# ring_counter.net
KiCad netlist of a schematic drawn in EAGLE
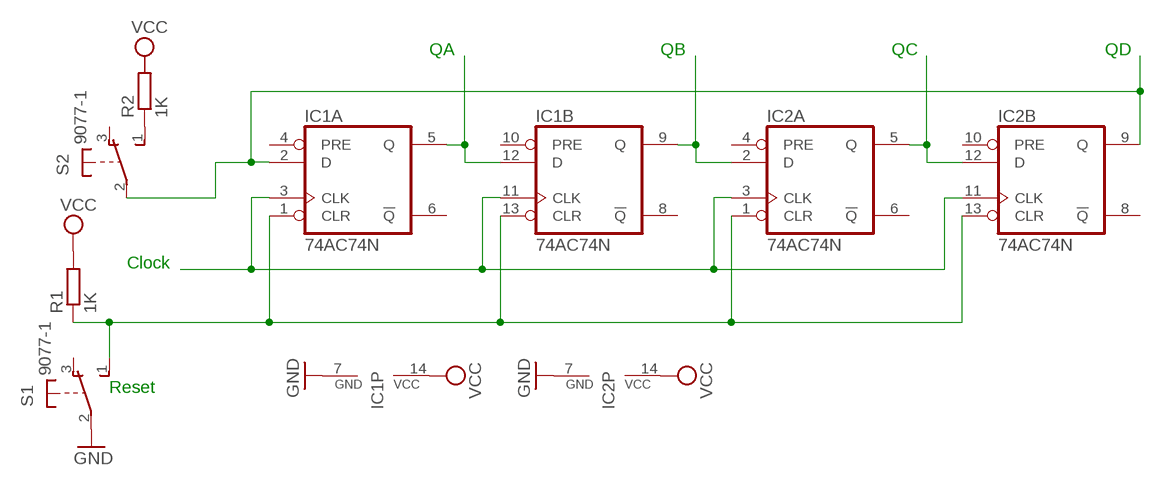
[diagram p0: schematic, sheet 1]

(export (version "E")
  (design (tool "Eeschema 10.0.6"))
  (components
    (comp (ref "IC1")
      (value "74AC74N")
      (footprint "eagle-import:DIL14")
      (libsource (lib "eagle-import") (part "7474NAC"))
    )
    (comp (ref "IC2")
      (value "74AC74N")
      (footprint "eagle-import:DIL14")
      (libsource (lib "eagle-import") (part "7474NAC"))
    )
    (comp (ref "R1")
      (value "1K")
      (footprint "eagle-import:0204_7")
      (libsource (lib "eagle-import") (part "R-EU_0204/7"))
    )
    (comp (ref "R2")
      (value "1K")
      (footprint "eagle-import:0204_7")
      (libsource (lib "eagle-import") (part "R-EU_0204/7"))
    )
    (comp (ref "S1")
      (value "9077-1")
      (footprint "eagle-import:9077-1")
      (libsource (lib "eagle-import") (part "9077-1"))
    )
    (comp (ref "S2")
      (value "9077-1")
      (footprint "eagle-import:9077-1")
      (libsource (lib "eagle-import") (part "9077-1"))
    )
  )
  (nets
    (net (code "1") (name "GND") (class "Default")
      (node (ref "IC1") (pin "7") (pinfunction "GND_7") (pintype "power_in"))
      (node (ref "IC2") (pin "7") (pinfunction "GND_7") (pintype "power_in"))
      (node (ref "S1") (pin "2") (pinfunction "P_2") (pintype "passive"))
    )
    (net (code "2") (name "Net-(IC1A-CLK)") (class "Default")
      (node (ref "IC1") (pin "11") (pinfunction "CLK_11") (pintype "input"))
      (node (ref "IC1") (pin "3") (pinfunction "CLK_3") (pintype "input"))
      (node (ref "IC2") (pin "11") (pinfunction "CLK_11") (pintype "input"))
      (node (ref "IC2") (pin "3") (pinfunction "CLK_3") (pintype "input"))
    )
    (net (code "3") (name "Net-(IC1A-CLR)") (class "Default")
      (node (ref "IC1") (pin "1") (pinfunction "CLR_1") (pintype "input"))
      (node (ref "IC1") (pin "13") (pinfunction "CLR_13") (pintype "input"))
      (node (ref "IC2") (pin "1") (pinfunction "CLR_1") (pintype "input"))
      (node (ref "IC2") (pin "13") (pinfunction "CLR_13") (pintype "input"))
      (node (ref "R1") (pin "1") (pinfunction "1_1") (pintype "passive"))
      (node (ref "S1") (pin "1") (pinfunction "S_1") (pintype "passive"))
    )
    (net (code "4") (name "Net-(IC1A-D)") (class "Default")
      (node (ref "IC1") (pin "2") (pinfunction "D_2") (pintype "input"))
      (node (ref "IC2") (pin "9") (pinfunction "Q_9") (pintype "output"))
      (node (ref "S2") (pin "2") (pinfunction "P_2") (pintype "passive"))
    )
    (net (code "5") (name "Net-(IC1A-Q)") (class "Default")
      (node (ref "IC1") (pin "12") (pinfunction "D_12") (pintype "input"))
      (node (ref "IC1") (pin "5") (pinfunction "Q_5") (pintype "output"))
    )
    (net (code "6") (name "Net-(IC1B-Q)") (class "Default")
      (node (ref "IC1") (pin "9") (pinfunction "Q_9") (pintype "output"))
      (node (ref "IC2") (pin "2") (pinfunction "D_2") (pintype "input"))
    )
    (net (code "7") (name "Net-(IC2A-Q)") (class "Default")
      (node (ref "IC2") (pin "12") (pinfunction "D_12") (pintype "input"))
      (node (ref "IC2") (pin "5") (pinfunction "Q_5") (pintype "output"))
    )
    (net (code "8") (name "Net-(S2-S)") (class "Default")
      (node (ref "R2") (pin "1") (pinfunction "1_1") (pintype "passive"))
      (node (ref "S2") (pin "1") (pinfunction "S_1") (pintype "passive"))
    )
    (net (code "9") (name "VCC") (class "Default")
      (node (ref "IC1") (pin "14") (pinfunction "VCC_14") (pintype "power_in"))
      (node (ref "IC2") (pin "14") (pinfunction "VCC_14") (pintype "power_in"))
      (node (ref "R1") (pin "2") (pinfunction "2_2") (pintype "passive"))
    )
    (net (code "10") (name "unconnected-(IC1A-PRE-Pad4)") (class "Default")
      (node (ref "IC1") (pin "4") (pinfunction "PRE_4") (pintype "input"))
    )
    (net (code "11") (name "unconnected-(IC1A-~{Q}-Pad6)") (class "Default")
      (node (ref "IC1") (pin "6") (pinfunction "~{Q}_6") (pintype "output"))
    )
    (net (code "12") (name "unconnected-(IC1B-PRE-Pad10)") (class "Default")
      (node (ref "IC1") (pin "10") (pinfunction "PRE_10") (pintype "input"))
    )
    (net (code "13") (name "unconnected-(IC1B-~{Q}-Pad8)") (class "Default")
      (node (ref "IC1") (pin "8") (pinfunction "~{Q}_8") (pintype "output"))
    )
    (net (code "14") (name "unconnected-(IC2A-PRE-Pad4)") (class "Default")
      (node (ref "IC2") (pin "4") (pinfunction "PRE_4") (pintype "input"))
    )
    (net (code "15") (name "unconnected-(IC2A-~{Q}-Pad6)") (class "Default")
      (node (ref "IC2") (pin "6") (pinfunction "~{Q}_6") (pintype "output"))
    )
    (net (code "16") (name "unconnected-(IC2B-PRE-Pad10)") (class "Default")
      (node (ref "IC2") (pin "10") (pinfunction "PRE_10") (pintype "input"))
    )
    (net (code "17") (name "unconnected-(IC2B-~{Q}-Pad8)") (class "Default")
      (node (ref "IC2") (pin "8") (pinfunction "~{Q}_8") (pintype "output"))
    )
    (net (code "18") (name "unconnected-(R2-Pad2)") (class "Default")
      (node (ref "R2") (pin "2") (pinfunction "2_2") (pintype "passive"))
    )
    (net (code "19") (name "unconnected-(S1-O-Pad3)") (class "Default")
      (node (ref "S1") (pin "3") (pinfunction "O_3") (pintype "passive"))
    )
    (net (code "20") (name "unconnected-(S2-O-Pad3)") (class "Default")
      (node (ref "S2") (pin "3") (pinfunction "O_3") (pintype "passive"))
    )
  )
)
